# Connectors.net
KiCad netlist of a schematic drawn in Altium Designer
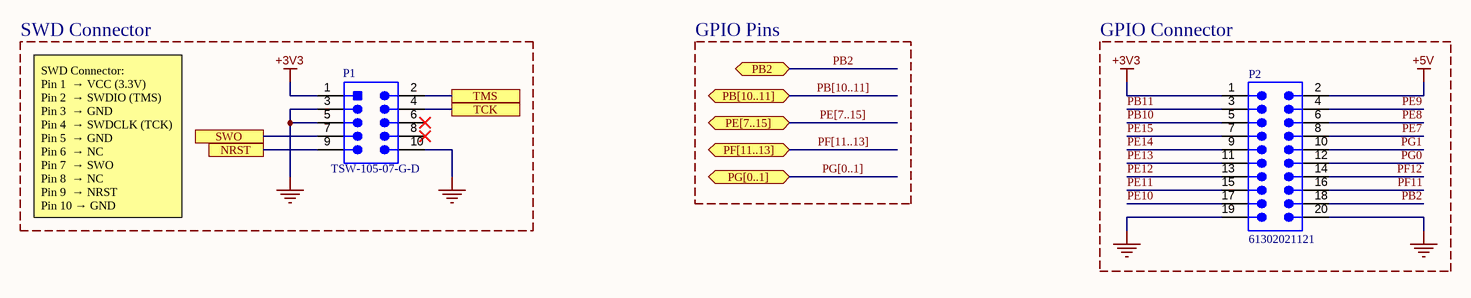
[diagram p0: Connectors.SchDoc]

(export (version "E")
  (design (tool "Eeschema 10.0.6"))
  (components
    (comp (ref "P1")
      (value "TSW-105-07-G-D")
      (footprint "SMTC-TSW-105-07-G-D_V")
      (fields (field (name "MANUFACTURER") "Samtec-Inc."))
      (libsource (lib "Altium Content Vault") (part "CN-2P-M-R10"))
    )
    (comp (ref "P2")
      (value "61302021121")
      (footprint "61302021121")
      (description "THT Vertical Pin Header WR-PHD, Pitch 2.54 mm, Dual Row, 20 pins")
      (libsource (lib "Altium Content Vault") (part "Header_Male_2R_20P"))
    )
  )
  (nets
    (net (code "2") (name "+3V3") (class "Default")
      (node (ref "P1") (pin "1") (pinfunction "1_1") (pintype "passive"))
      (node (ref "P2") (pin "1") (pinfunction "1_1") (pintype "passive"))
    )
    (net (code "3") (name "+5V") (class "Default")
      (node (ref "P2") (pin "2") (pinfunction "2_2") (pintype "passive"))
    )
    (net (code "4") (name "/NRST") (class "Default")
      (node (ref "P1") (pin "9") (pinfunction "9_9") (pintype "passive"))
    )
    (net (code "5") (name "/PB2") (class "Default")
      (node (ref "P2") (pin "18") (pinfunction "18_18") (pintype "passive"))
    )
    (net (code "6") (name "/PB10") (class "Default")
      (node (ref "P2") (pin "5") (pinfunction "5_5") (pintype "passive"))
    )
    (net (code "7") (name "/PB11") (class "Default")
      (node (ref "P2") (pin "3") (pinfunction "3_3") (pintype "passive"))
    )
    (net (code "9") (name "/PE7") (class "Default")
      (node (ref "P2") (pin "8") (pinfunction "8_8") (pintype "passive"))
    )
    (net (code "10") (name "/PE8") (class "Default")
      (node (ref "P2") (pin "6") (pinfunction "6_6") (pintype "passive"))
    )
    (net (code "11") (name "/PE9") (class "Default")
      (node (ref "P2") (pin "4") (pinfunction "4_4") (pintype "passive"))
    )
    (net (code "12") (name "/PE10") (class "Default")
      (node (ref "P2") (pin "17") (pinfunction "17_17") (pintype "passive"))
    )
    (net (code "13") (name "/PE11") (class "Default")
      (node (ref "P2") (pin "15") (pinfunction "15_15") (pintype "passive"))
    )
    (net (code "14") (name "/PE12") (class "Default")
      (node (ref "P2") (pin "13") (pinfunction "13_13") (pintype "passive"))
    )
    (net (code "15") (name "/PE13") (class "Default")
      (node (ref "P2") (pin "11") (pinfunction "11_11") (pintype "passive"))
    )
    (net (code "16") (name "/PE14") (class "Default")
      (node (ref "P2") (pin "9") (pinfunction "9_9") (pintype "passive"))
    )
    (net (code "17") (name "/PE15") (class "Default")
      (node (ref "P2") (pin "7") (pinfunction "7_7") (pintype "passive"))
    )
    (net (code "19") (name "/PF11") (class "Default")
      (node (ref "P2") (pin "16") (pinfunction "16_16") (pintype "passive"))
    )
    (net (code "20") (name "/PF12") (class "Default")
      (node (ref "P2") (pin "14") (pinfunction "14_14") (pintype "passive"))
    )
    (net (code "22") (name "/PG0") (class "Default")
      (node (ref "P2") (pin "12") (pinfunction "12_12") (pintype "passive"))
    )
    (net (code "23") (name "/PG1") (class "Default")
      (node (ref "P2") (pin "10") (pinfunction "10_10") (pintype "passive"))
    )
    (net (code "25") (name "/SWO") (class "Default")
      (node (ref "P1") (pin "7") (pinfunction "7_7") (pintype "passive"))
    )
    (net (code "26") (name "/TCK") (class "Default")
      (node (ref "P1") (pin "4") (pinfunction "4_4") (pintype "passive"))
    )
    (net (code "27") (name "/TMS") (class "Default")
      (node (ref "P1") (pin "2") (pinfunction "2_2") (pintype "passive"))
    )
    (net (code "28") (name "GND") (class "Default")
      (node (ref "P1") (pin "10") (pinfunction "10_10") (pintype "passive"))
      (node (ref "P1") (pin "3") (pinfunction "3_3") (pintype "passive"))
      (node (ref "P1") (pin "5") (pinfunction "5_5") (pintype "passive"))
      (node (ref "P2") (pin "19") (pinfunction "19_19") (pintype "passive"))
      (node (ref "P2") (pin "20") (pinfunction "20_20") (pintype "passive"))
    )
    (net (code "29") (name "unconnected-(P1-Pad6)") (class "Default")
      (node (ref "P1") (pin "6") (pinfunction "6_6") (pintype "passive+no_connect"))
    )
    (net (code "30") (name "unconnected-(P1-Pad8)") (class "Default")
      (node (ref "P1") (pin "8") (pinfunction "8_8") (pintype "passive+no_connect"))
    )
  )
)
